# Power_Supply.net
KiCad netlist of a schematic drawn in Altium Designer
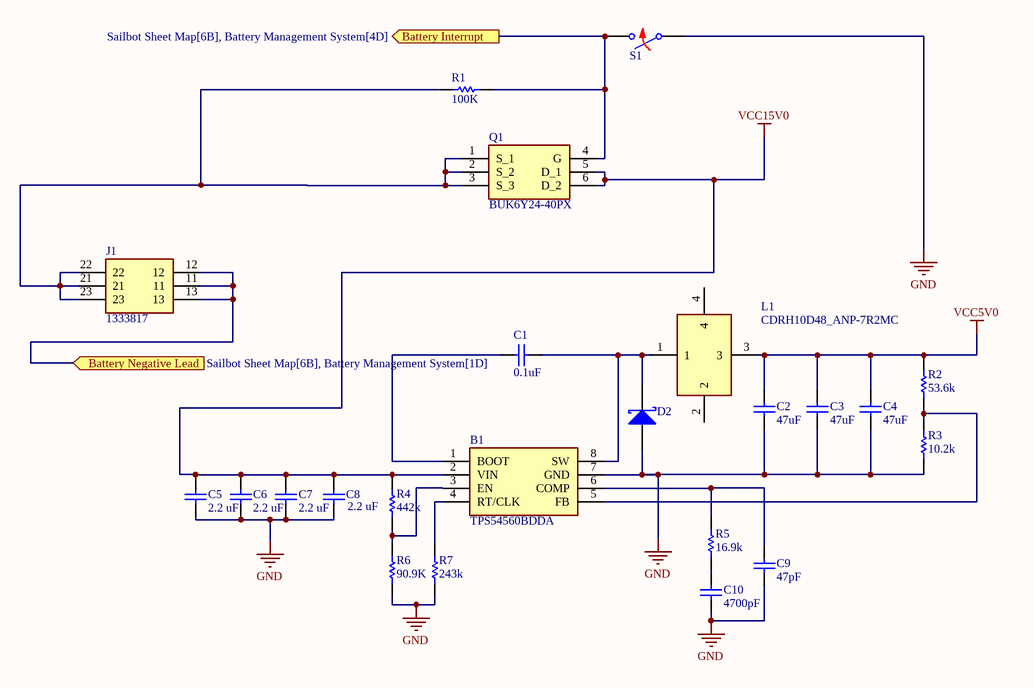
[diagram p0: Power Supply.SchDoc]

(export (version "E")
  (design (tool "Eeschema 10.0.6"))
  (components
    (comp (ref "B1")
      (value "TPS54560BDDA")
      (footprint "SOIC127P600X170-8N")
      (description "Switching Voltage Regulators A 595-TPS54560BDDAR")
      (fields (field (name "MOUSER PART NUMBER") "595-TPS54560BDDA"))
      (libsource (lib "Sailbot Library") (part "TPS54560BDDA"))
    )
    (comp (ref "C1")
      (value "0.1uF")
      (footprint "C0805")
      (description "Capacitor")
      (libsource (lib "Simulation Generic Components") (part "Capacitor"))
    )
    (comp (ref "C2")
      (value "47uF")
      (footprint "C0805")
      (description "Capacitor")
      (libsource (lib "Simulation Generic Components") (part "Capacitor"))
    )
    (comp (ref "C3")
      (value "47uF")
      (footprint "C0805")
      (description "Capacitor")
      (libsource (lib "Simulation Generic Components") (part "Capacitor"))
    )
    (comp (ref "C4")
      (value "47uF")
      (footprint "C0805")
      (description "Capacitor")
      (libsource (lib "Simulation Generic Components") (part "Capacitor"))
    )
    (comp (ref "C5")
      (value "2.2 uF")
      (footprint "C0805")
      (description "Capacitor")
      (libsource (lib "Simulation Generic Components") (part "Capacitor"))
    )
    (comp (ref "C6")
      (value "2.2 uF")
      (footprint "C0805")
      (description "Capacitor")
      (libsource (lib "Simulation Generic Components") (part "Capacitor"))
    )
    (comp (ref "C7")
      (value "2.2 uF")
      (footprint "C0805")
      (description "Capacitor")
      (libsource (lib "Simulation Generic Components") (part "Capacitor"))
    )
    (comp (ref "C8")
      (value "2.2 uF")
      (footprint "C0805")
      (description "Capacitor")
      (libsource (lib "Simulation Generic Components") (part "Capacitor"))
    )
    (comp (ref "C9")
      (value "47pF")
      (footprint "C0805")
      (description "Capacitor")
      (libsource (lib "Simulation Generic Components") (part "Capacitor"))
    )
    (comp (ref "C10")
      (value "4700pF")
      (footprint "C0805")
      (description "Capacitor")
      (libsource (lib "Simulation Generic Components") (part "Capacitor"))
    )
    (comp (ref "D2")
      (value "Shottky Diode")
      (footprint "DIOM7959X250N")
      (libsource (lib "Simulation Generic Components") (part "Shottky Diode"))
    )
    (comp (ref "J1")
      (value "1333817")
      (footprint "1333817")
      (description "Pluggable Terminal Blocks LPTA 16/ 2-10,0-ZB")
      (fields (field (name "MOUSER PART NUMBER") "651-1333817"))
      (libsource (lib "Sailbot Library") (part "1333817"))
    )
    (comp (ref "L1")
      (value "CDRH10D48_ANP-7R2MC")
      (footprint "CDRH10D48ANP7R2MC")
      (description "Fixed Inductors SMD Power Inductor")
      (fields
        (field (name "MOUSER PART NUMBER") "851-CDRH10D48/ANP7R2")
        (field (name "MANUFACTURER_PART_NUMBER") "CDRH10D48/ANP-7R2MC")
      )
      (libsource (lib "Sailbot Library") (part "CDRH10D48_ANP-7R2MC"))
    )
    (comp (ref "Q1")
      (value "BUK6Y24-40PX")
      (footprint "BUK6Y2440PX")
      (description "NEXPERIA - BUK6Y24-40PX - Power MOSFET, P Channel, 40 V, 39 A, 0.019 ohm, LFPAK56, Surface Mount")
      (fields (field (name "MOUSER PART NUMBER") "771-BUK6Y24-40PX"))
      (libsource (lib "Sailbot Library") (part "BUK6Y24-40PX"))
    )
    (comp (ref "R1")
      (value "100K")
      (footprint "6-0805_M")
      (description "Resistor")
      (libsource (lib "Simulation Generic Components") (part "Resistor"))
    )
    (comp (ref "R2")
      (value "53.6k")
      (footprint "6-0805_M")
      (description "Resistor")
      (libsource (lib "Simulation Generic Components") (part "Resistor"))
    )
    (comp (ref "R3")
      (value "10.2k")
      (footprint "6-0805_M")
      (description "Resistor")
      (libsource (lib "Simulation Generic Components") (part "Resistor"))
    )
    (comp (ref "R4")
      (value "442k")
      (footprint "6-0805_M")
      (description "Resistor")
      (libsource (lib "Simulation Generic Components") (part "Resistor"))
    )
    (comp (ref "R5")
      (value "16.9k")
      (footprint "6-0805_M")
      (description "Resistor")
      (libsource (lib "Simulation Generic Components") (part "Resistor"))
    )
    (comp (ref "R6")
      (value "90.9K")
      (footprint "6-0805_M")
      (description "Resistor")
      (libsource (lib "Simulation Generic Components") (part "Resistor"))
    )
    (comp (ref "R7")
      (value "243k")
      (footprint "6-0805_M")
      (description "Resistor")
      (libsource (lib "Simulation Generic Components") (part "Resistor"))
    )
    (comp (ref "S1")
      (value "Switch Normally Opened")
      (libsource (lib "Simulation Generic Components") (part "SW NO"))
    )
  )
  (nets
    (net (code "1") (name "/Battery Interrupt") (class "Default")
      (node (ref "Q1") (pin "4") (pinfunction "G_4") (pintype "passive"))
      (node (ref "R1") (pin "2") (pinfunction "2_2") (pintype "passive"))
      (node (ref "S1") (pin "2") (pinfunction "2_2") (pintype "passive"))
    )
    (net (code "2") (name "/Battery Negative Lead") (class "Default")
      (node (ref "J1") (pin "11") (pinfunction "11_11") (pintype "passive"))
      (node (ref "J1") (pin "12") (pinfunction "12_12") (pintype "passive"))
      (node (ref "J1") (pin "13") (pinfunction "13_13") (pintype "passive"))
    )
    (net (code "3") (name "GND") (class "Default")
      (node (ref "B1") (pin "7") (pinfunction "GND_7") (pintype "passive"))
      (node (ref "C10") (pin "1") (pinfunction "1_1") (pintype "passive"))
      (node (ref "C2") (pin "1") (pinfunction "1_1") (pintype "passive"))
      (node (ref "C3") (pin "1") (pinfunction "1_1") (pintype "passive"))
      (node (ref "C4") (pin "1") (pinfunction "1_1") (pintype "passive"))
      (node (ref "C5") (pin "1") (pinfunction "1_1") (pintype "passive"))
      (node (ref "C6") (pin "1") (pinfunction "1_1") (pintype "passive"))
      (node (ref "C7") (pin "1") (pinfunction "1_1") (pintype "passive"))
      (node (ref "C8") (pin "1") (pinfunction "1_1") (pintype "passive"))
      (node (ref "C9") (pin "1") (pinfunction "1_1") (pintype "passive"))
      (node (ref "D2") (pin "1") (pinfunction "A_1") (pintype "passive"))
      (node (ref "R3") (pin "1") (pinfunction "1_1") (pintype "passive"))
      (node (ref "R6") (pin "1") (pinfunction "1_1") (pintype "passive"))
      (node (ref "R7") (pin "1") (pinfunction "1_1") (pintype "passive"))
      (node (ref "S1") (pin "1") (pinfunction "1_1") (pintype "passive"))
    )
    (net (code "4") (name "Net-(B1-BOOT)") (class "Default")
      (node (ref "B1") (pin "1") (pinfunction "BOOT_1") (pintype "passive"))
      (node (ref "C1") (pin "1") (pinfunction "1_1") (pintype "passive"))
    )
    (net (code "5") (name "Net-(B1-COMP)") (class "Default")
      (node (ref "B1") (pin "6") (pinfunction "COMP_6") (pintype "passive"))
      (node (ref "C9") (pin "2") (pinfunction "2_2") (pintype "passive"))
      (node (ref "R5") (pin "2") (pinfunction "2_2") (pintype "passive"))
    )
    (net (code "6") (name "Net-(B1-EN)") (class "Default")
      (node (ref "B1") (pin "3") (pinfunction "EN_3") (pintype "passive"))
      (node (ref "R4") (pin "1") (pinfunction "1_1") (pintype "passive"))
      (node (ref "R6") (pin "2") (pinfunction "2_2") (pintype "passive"))
    )
    (net (code "7") (name "Net-(B1-FB)") (class "Default")
      (node (ref "B1") (pin "5") (pinfunction "FB_5") (pintype "passive"))
      (node (ref "R2") (pin "1") (pinfunction "1_1") (pintype "passive"))
      (node (ref "R3") (pin "2") (pinfunction "2_2") (pintype "passive"))
    )
    (net (code "8") (name "Net-(B1-RT{slash}CLK)") (class "Default")
      (node (ref "B1") (pin "4") (pinfunction "RT/CLK_4") (pintype "passive"))
      (node (ref "R7") (pin "2") (pinfunction "2_2") (pintype "passive"))
    )
    (net (code "9") (name "Net-(B1-SW)") (class "Default")
      (node (ref "B1") (pin "8") (pinfunction "SW_8") (pintype "passive"))
      (node (ref "C1") (pin "2") (pinfunction "2_2") (pintype "passive"))
      (node (ref "D2") (pin "2") (pinfunction "K_2") (pintype "passive"))
      (node (ref "L1") (pin "1") (pinfunction "1_1") (pintype "passive"))
    )
    (net (code "10") (name "Net-(C10-Pad2)") (class "Default")
      (node (ref "C10") (pin "2") (pinfunction "2_2") (pintype "passive"))
      (node (ref "R5") (pin "1") (pinfunction "1_1") (pintype "passive"))
    )
    (net (code "11") (name "Net-(Q1-S_1)") (class "Default")
      (node (ref "J1") (pin "21") (pinfunction "21_21") (pintype "passive"))
      (node (ref "J1") (pin "22") (pinfunction "22_22") (pintype "passive"))
      (node (ref "J1") (pin "23") (pinfunction "23_23") (pintype "passive"))
      (node (ref "Q1") (pin "1") (pinfunction "S_1_1") (pintype "passive"))
      (node (ref "Q1") (pin "2") (pinfunction "S_2_2") (pintype "passive"))
      (node (ref "Q1") (pin "3") (pinfunction "S_3_3") (pintype "passive"))
      (node (ref "R1") (pin "1") (pinfunction "1_1") (pintype "passive"))
    )
    (net (code "12") (name "VCC5V0") (class "Default")
      (node (ref "C2") (pin "2") (pinfunction "2_2") (pintype "passive"))
      (node (ref "C3") (pin "2") (pinfunction "2_2") (pintype "passive"))
      (node (ref "C4") (pin "2") (pinfunction "2_2") (pintype "passive"))
      (node (ref "L1") (pin "3") (pinfunction "3_3") (pintype "passive"))
      (node (ref "R2") (pin "2") (pinfunction "2_2") (pintype "passive"))
    )
    (net (code "13") (name "VCC15V0") (class "Default")
      (node (ref "B1") (pin "2") (pinfunction "VIN_2") (pintype "passive"))
      (node (ref "C5") (pin "2") (pinfunction "2_2") (pintype "passive"))
      (node (ref "C6") (pin "2") (pinfunction "2_2") (pintype "passive"))
      (node (ref "C7") (pin "2") (pinfunction "2_2") (pintype "passive"))
      (node (ref "C8") (pin "2") (pinfunction "2_2") (pintype "passive"))
      (node (ref "Q1") (pin "5") (pinfunction "D_1_5") (pintype "passive"))
      (node (ref "Q1") (pin "6") (pinfunction "D_2_6") (pintype "passive"))
      (node (ref "R4") (pin "2") (pinfunction "2_2") (pintype "passive"))
    )
    (net (code "14") (name "unconnected-(L1-Pad2)") (class "Default")
      (node (ref "L1") (pin "2") (pinfunction "2_2") (pintype "passive"))
    )
    (net (code "15") (name "unconnected-(L1-Pad4)") (class "Default")
      (node (ref "L1") (pin "4") (pinfunction "4_4") (pintype "passive"))
    )
  )
)
